# Adafruit_Speaker_Bonnet_rev_D.net
KiCad netlist of a schematic drawn in EAGLE
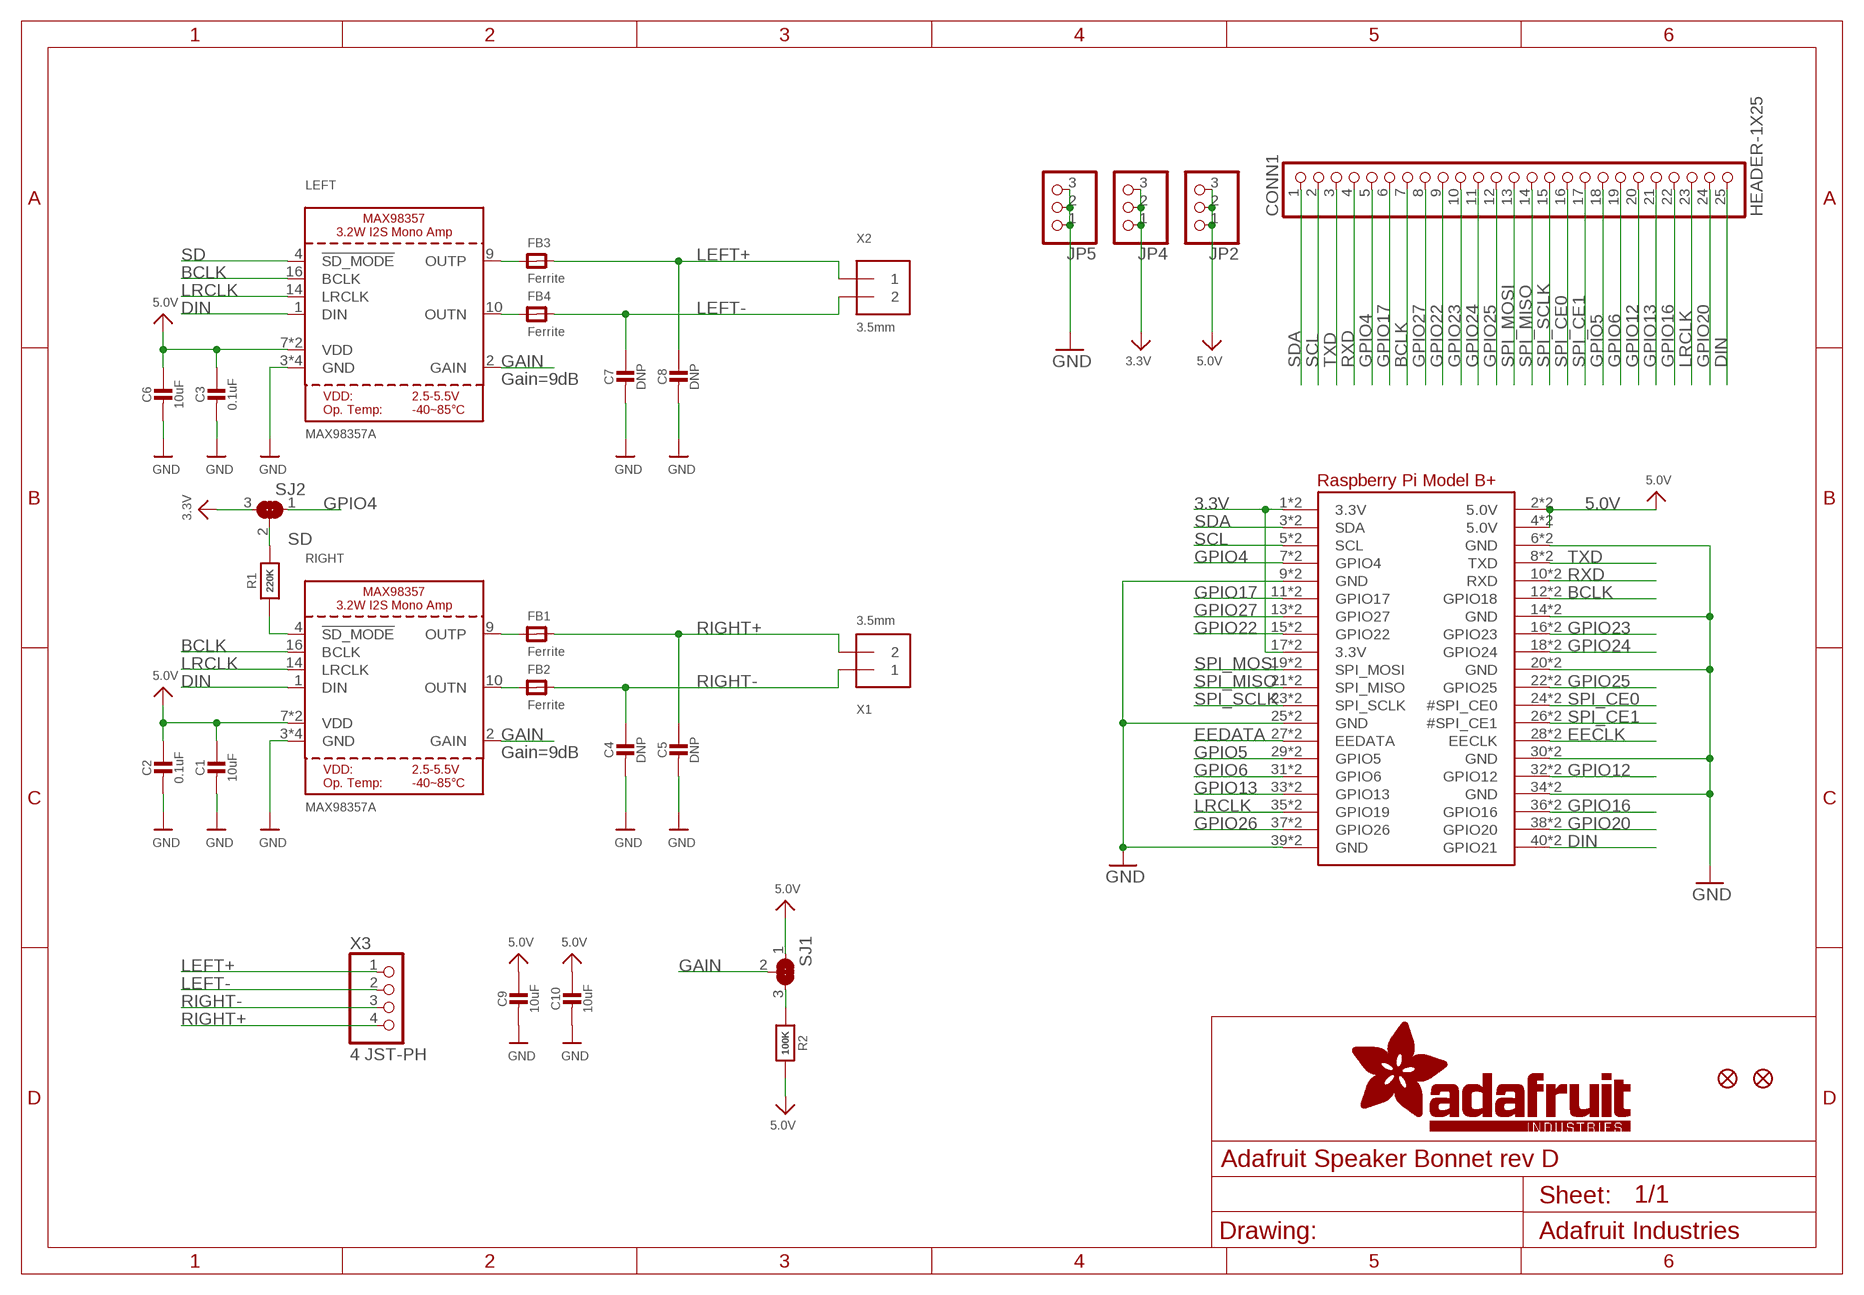
[diagram p0: schematic, sheet 1]

(export (version "E")
  (design (tool "Eeschema 10.0.6"))
  (components
    (comp (ref "C1")
      (value "10uF")
      (footprint "eagle-import:0805-NO")
      (libsource (lib "eagle-import") (part "CAP_CERAMIC0805-NOOUTLINE"))
    )
    (comp (ref "C2")
      (value "0.1uF")
      (footprint "eagle-import:0805-NO")
      (libsource (lib "eagle-import") (part "CAP_CERAMIC0805-NOOUTLINE"))
    )
    (comp (ref "C3")
      (value "0.1uF")
      (footprint "eagle-import:0805-NO")
      (libsource (lib "eagle-import") (part "CAP_CERAMIC0805-NOOUTLINE"))
    )
    (comp (ref "C4")
      (value "DNP")
      (footprint "eagle-import:0805-NO")
      (libsource (lib "eagle-import") (part "CAP_CERAMIC0805-NOOUTLINE"))
    )
    (comp (ref "C5")
      (value "DNP")
      (footprint "eagle-import:0805-NO")
      (libsource (lib "eagle-import") (part "CAP_CERAMIC0805-NOOUTLINE"))
    )
    (comp (ref "C6")
      (value "10uF")
      (footprint "eagle-import:0805-NO")
      (libsource (lib "eagle-import") (part "CAP_CERAMIC0805-NOOUTLINE"))
    )
    (comp (ref "C7")
      (value "DNP")
      (footprint "eagle-import:0805-NO")
      (libsource (lib "eagle-import") (part "CAP_CERAMIC0805-NOOUTLINE"))
    )
    (comp (ref "C8")
      (value "DNP")
      (footprint "eagle-import:0805-NO")
      (libsource (lib "eagle-import") (part "CAP_CERAMIC0805-NOOUTLINE"))
    )
    (comp (ref "C9")
      (value "10uF")
      (footprint "eagle-import:0805-NO")
      (libsource (lib "eagle-import") (part "CAP_CERAMIC0805-NOOUTLINE"))
    )
    (comp (ref "C10")
      (value "10uF")
      (footprint "eagle-import:0805-NO")
      (libsource (lib "eagle-import") (part "CAP_CERAMIC0805-NOOUTLINE"))
    )
    (comp (ref "CONN1")
      (value "HEADER-1X25")
      (footprint "eagle-import:1X25_ROUND_70MIL")
      (libsource (lib "eagle-import") (part "HEADER-1X25"))
    )
    (comp (ref "FB1")
      (value "Ferrite")
      (footprint "eagle-import:0805-NO")
      (libsource (lib "eagle-import") (part "FERRITE-0805NO"))
    )
    (comp (ref "FB2")
      (value "Ferrite")
      (footprint "eagle-import:0805-NO")
      (libsource (lib "eagle-import") (part "FERRITE-0805NO"))
    )
    (comp (ref "FB3")
      (value "Ferrite")
      (footprint "eagle-import:0805-NO")
      (libsource (lib "eagle-import") (part "FERRITE-0805NO"))
    )
    (comp (ref "FB4")
      (value "Ferrite")
      (footprint "eagle-import:0805-NO")
      (libsource (lib "eagle-import") (part "FERRITE-0805NO"))
    )
    (comp (ref "FID1")
      (value "FIDUCIAL_1MM")
      (footprint "eagle-import:FIDUCIAL_1MM")
      (libsource (lib "eagle-import") (part "FIDUCIAL_1MM"))
    )
    (comp (ref "FID2")
      (value "FIDUCIAL_1MM")
      (footprint "eagle-import:FIDUCIAL_1MM")
      (libsource (lib "eagle-import") (part "FIDUCIAL_1MM"))
    )
    (comp (ref "JP2")
      (value "HEADER-1X376MIL")
      (footprint "eagle-import:1X03_ROUND_76")
      (libsource (lib "eagle-import") (part "HEADER-1X376MIL"))
    )
    (comp (ref "JP4")
      (value "HEADER-1X376MIL")
      (footprint "eagle-import:1X03_ROUND_76")
      (libsource (lib "eagle-import") (part "HEADER-1X376MIL"))
    )
    (comp (ref "JP5")
      (value "HEADER-1X376MIL")
      (footprint "eagle-import:1X03_ROUND_76")
      (libsource (lib "eagle-import") (part "HEADER-1X376MIL"))
    )
    (comp (ref "LEFT")
      (value "MAX98357A")
      (footprint "eagle-import:QFN16_3MM")
      (libsource (lib "eagle-import") (part "AUDIOAMP_MAX98357"))
    )
    (comp (ref "R1")
      (value "220K")
      (footprint "eagle-import:0805-NO")
      (libsource (lib "eagle-import") (part "RESISTOR0805_NOOUTLINE"))
    )
    (comp (ref "R2")
      (value "100K")
      (footprint "eagle-import:0805-NO")
      (libsource (lib "eagle-import") (part "RESISTOR0805_NOOUTLINE"))
    )
    (comp (ref "RIGHT")
      (value "MAX98357A")
      (footprint "eagle-import:QFN16_3MM")
      (libsource (lib "eagle-import") (part "AUDIOAMP_MAX98357"))
    )
    (comp (ref "RPI1")
      (value "RASPBERRYPI_BPLUS_BONNET_THMSMT")
      (footprint "eagle-import:PI_BONNET_THMSMT")
      (libsource (lib "eagle-import") (part "RASPBERRYPI_BPLUS_BONNET_THMSMT"))
    )
    (comp (ref "SJ1")
      (value "SOLDERJUMPER_2WAY")
      (footprint "eagle-import:SOLDERJUMPER_2WAY_OPEN_NOPASTE")
      (libsource (lib "eagle-import") (part "SOLDERJUMPER_2WAY"))
    )
    (comp (ref "SJ2")
      (value "SOLDERJUMPER_2WAY")
      (footprint "eagle-import:SOLDERJUMPER_2WAY_OPEN_NOPASTE")
      (libsource (lib "eagle-import") (part "SOLDERJUMPER_2WAY"))
    )
    (comp (ref "X1")
      (value "3.5mm")
      (footprint "eagle-import:TERMBLOCK_1X2-3.5MM")
      (fields (field (name "ROT") "0"))
      (libsource (lib "eagle-import") (part "TERMBLOCK_1X2_3.5MM"))
    )
    (comp (ref "X2")
      (value "3.5mm")
      (footprint "eagle-import:TERMBLOCK_1X2-3.5MM")
      (fields (field (name "ROT") "0"))
      (libsource (lib "eagle-import") (part "TERMBLOCK_1X2_3.5MM"))
    )
    (comp (ref "X3")
      (value "4 JST-PH")
      (footprint "eagle-import:JSTPH4")
      (libsource (lib "eagle-import") (part "CON_JST_PH_4PIN"))
    )
  )
  (nets
    (net (code "1") (name "/BCLK") (class "Default")
      (node (ref "CONN1") (pin "7") (pinfunction "7_7") (pintype "passive"))
      (node (ref "LEFT") (pin "16") (pinfunction "BCLK_16") (pintype "bidirectional"))
      (node (ref "RIGHT") (pin "16") (pinfunction "BCLK_16") (pintype "bidirectional"))
      (node (ref "RPI1") (pin "12") (pinfunction "GPIO18_12") (pintype "bidirectional"))
      (node (ref "RPI1") (pin "S12") (pinfunction "GPIO18_S12") (pintype "bidirectional"))
    )
    (net (code "2") (name "/DIN") (class "Default")
      (node (ref "CONN1") (pin "25") (pinfunction "25_25") (pintype "passive"))
      (node (ref "LEFT") (pin "1") (pinfunction "DIN_1") (pintype "bidirectional"))
      (node (ref "RIGHT") (pin "1") (pinfunction "DIN_1") (pintype "bidirectional"))
      (node (ref "RPI1") (pin "40") (pinfunction "GPIO21_40") (pintype "bidirectional"))
      (node (ref "RPI1") (pin "S40") (pinfunction "GPIO21_S40") (pintype "bidirectional"))
    )
    (net (code "3") (name "/EECLK") (class "Default")
      (node (ref "RPI1") (pin "28") (pinfunction "EECLK_28") (pintype "bidirectional"))
      (node (ref "RPI1") (pin "S28") (pinfunction "EECLK_S28") (pintype "bidirectional"))
    )
    (net (code "4") (name "/EEDATA") (class "Default")
      (node (ref "RPI1") (pin "27") (pinfunction "EEDATA_27") (pintype "bidirectional"))
      (node (ref "RPI1") (pin "S27") (pinfunction "EEDATA_S27") (pintype "bidirectional"))
    )
    (net (code "5") (name "/GAIN") (class "Default")
      (node (ref "LEFT") (pin "2") (pinfunction "GAIN_2") (pintype "bidirectional"))
      (node (ref "RIGHT") (pin "2") (pinfunction "GAIN_2") (pintype "bidirectional"))
      (node (ref "SJ1") (pin "2") (pinfunction "2_2") (pintype "passive"))
    )
    (net (code "6") (name "/GPIO4") (class "Default")
      (node (ref "CONN1") (pin "5") (pinfunction "5_5") (pintype "passive"))
      (node (ref "RPI1") (pin "7") (pinfunction "GPIO4_7") (pintype "bidirectional"))
      (node (ref "RPI1") (pin "S7") (pinfunction "GPIO4_S7") (pintype "bidirectional"))
      (node (ref "SJ2") (pin "1") (pinfunction "1_1") (pintype "passive"))
    )
    (net (code "7") (name "/GPIO5") (class "Default")
      (node (ref "CONN1") (pin "18") (pinfunction "18_18") (pintype "passive"))
      (node (ref "RPI1") (pin "29") (pinfunction "GPIO5_29") (pintype "bidirectional"))
      (node (ref "RPI1") (pin "S29") (pinfunction "GPIO5_S29") (pintype "bidirectional"))
    )
    (net (code "8") (name "/GPIO6") (class "Default")
      (node (ref "CONN1") (pin "19") (pinfunction "19_19") (pintype "passive"))
      (node (ref "RPI1") (pin "31") (pinfunction "GPIO6_31") (pintype "bidirectional"))
      (node (ref "RPI1") (pin "S31") (pinfunction "GPIO6_S31") (pintype "bidirectional"))
    )
    (net (code "9") (name "/GPIO12") (class "Default")
      (node (ref "CONN1") (pin "20") (pinfunction "20_20") (pintype "passive"))
      (node (ref "RPI1") (pin "32") (pinfunction "GPIO12_32") (pintype "bidirectional"))
      (node (ref "RPI1") (pin "S32") (pinfunction "GPIO12_S32") (pintype "bidirectional"))
    )
    (net (code "10") (name "/GPIO13") (class "Default")
      (node (ref "CONN1") (pin "21") (pinfunction "21_21") (pintype "passive"))
      (node (ref "RPI1") (pin "33") (pinfunction "GPIO13_33") (pintype "bidirectional"))
      (node (ref "RPI1") (pin "S33") (pinfunction "GPIO13_S33") (pintype "bidirectional"))
    )
    (net (code "11") (name "/GPIO16") (class "Default")
      (node (ref "CONN1") (pin "22") (pinfunction "22_22") (pintype "passive"))
      (node (ref "RPI1") (pin "36") (pinfunction "GPIO16_36") (pintype "bidirectional"))
      (node (ref "RPI1") (pin "S36") (pinfunction "GPIO16_S36") (pintype "bidirectional"))
    )
    (net (code "12") (name "/GPIO17") (class "Default")
      (node (ref "CONN1") (pin "6") (pinfunction "6_6") (pintype "passive"))
      (node (ref "RPI1") (pin "11") (pinfunction "GPIO17_11") (pintype "bidirectional"))
      (node (ref "RPI1") (pin "S11") (pinfunction "GPIO17_S11") (pintype "bidirectional"))
    )
    (net (code "13") (name "/GPIO20") (class "Default")
      (node (ref "CONN1") (pin "24") (pinfunction "24_24") (pintype "passive"))
      (node (ref "RPI1") (pin "38") (pinfunction "GPIO20_38") (pintype "bidirectional"))
      (node (ref "RPI1") (pin "S38") (pinfunction "GPIO20_S38") (pintype "bidirectional"))
    )
    (net (code "14") (name "/GPIO22") (class "Default")
      (node (ref "CONN1") (pin "9") (pinfunction "9_9") (pintype "passive"))
      (node (ref "RPI1") (pin "15") (pinfunction "GPIO22_15") (pintype "bidirectional"))
      (node (ref "RPI1") (pin "S15") (pinfunction "GPIO22_S15") (pintype "bidirectional"))
    )
    (net (code "15") (name "/GPIO23") (class "Default")
      (node (ref "CONN1") (pin "10") (pinfunction "10_10") (pintype "passive"))
      (node (ref "RPI1") (pin "16") (pinfunction "GPIO23_16") (pintype "bidirectional"))
      (node (ref "RPI1") (pin "S16") (pinfunction "GPIO23_S16") (pintype "bidirectional"))
    )
    (net (code "16") (name "/GPIO24") (class "Default")
      (node (ref "CONN1") (pin "11") (pinfunction "11_11") (pintype "passive"))
      (node (ref "RPI1") (pin "18") (pinfunction "GPIO24_18") (pintype "bidirectional"))
      (node (ref "RPI1") (pin "S18") (pinfunction "GPIO24_S18") (pintype "bidirectional"))
    )
    (net (code "17") (name "/GPIO25") (class "Default")
      (node (ref "CONN1") (pin "12") (pinfunction "12_12") (pintype "passive"))
      (node (ref "RPI1") (pin "22") (pinfunction "GPIO25_22") (pintype "bidirectional"))
      (node (ref "RPI1") (pin "S22") (pinfunction "GPIO25_S22") (pintype "bidirectional"))
    )
    (net (code "18") (name "/GPIO26") (class "Default")
      (node (ref "RPI1") (pin "37") (pinfunction "GPIO26_37") (pintype "bidirectional"))
      (node (ref "RPI1") (pin "S37") (pinfunction "GPIO26_S37") (pintype "bidirectional"))
    )
    (net (code "19") (name "/GPIO27") (class "Default")
      (node (ref "CONN1") (pin "8") (pinfunction "8_8") (pintype "passive"))
      (node (ref "RPI1") (pin "13") (pinfunction "GPIO27_13") (pintype "bidirectional"))
      (node (ref "RPI1") (pin "S13") (pinfunction "GPIO27_S13") (pintype "bidirectional"))
    )
    (net (code "20") (name "/LEFT+") (class "Default")
      (node (ref "C8") (pin "1") (pinfunction "1_1") (pintype "passive"))
      (node (ref "FB3") (pin "2") (pinfunction "P$2_2") (pintype "passive"))
      (node (ref "X2") (pin "1") (pinfunction "1_1") (pintype "passive"))
      (node (ref "X3") (pin "1") (pinfunction "1_1") (pintype "passive"))
    )
    (net (code "21") (name "/LEFT-") (class "Default")
      (node (ref "C7") (pin "1") (pinfunction "1_1") (pintype "passive"))
      (node (ref "FB4") (pin "2") (pinfunction "P$2_2") (pintype "passive"))
      (node (ref "X2") (pin "2") (pinfunction "2_2") (pintype "passive"))
      (node (ref "X3") (pin "2") (pinfunction "2_2") (pintype "passive"))
    )
    (net (code "22") (name "/LRCLK") (class "Default")
      (node (ref "CONN1") (pin "23") (pinfunction "23_23") (pintype "passive"))
      (node (ref "LEFT") (pin "14") (pinfunction "LRCLK_14") (pintype "bidirectional"))
      (node (ref "RIGHT") (pin "14") (pinfunction "LRCLK_14") (pintype "bidirectional"))
      (node (ref "RPI1") (pin "35") (pinfunction "GPIO19_35") (pintype "bidirectional"))
      (node (ref "RPI1") (pin "S35") (pinfunction "GPIO19_S35") (pintype "bidirectional"))
    )
    (net (code "23") (name "/RIGHT+") (class "Default")
      (node (ref "C5") (pin "1") (pinfunction "1_1") (pintype "passive"))
      (node (ref "FB1") (pin "2") (pinfunction "P$2_2") (pintype "passive"))
      (node (ref "X1") (pin "2") (pinfunction "2_2") (pintype "passive"))
      (node (ref "X3") (pin "4") (pinfunction "4_4") (pintype "passive"))
    )
    (net (code "24") (name "/RIGHT-") (class "Default")
      (node (ref "C4") (pin "1") (pinfunction "1_1") (pintype "passive"))
      (node (ref "FB2") (pin "2") (pinfunction "P$2_2") (pintype "passive"))
      (node (ref "X1") (pin "1") (pinfunction "1_1") (pintype "passive"))
      (node (ref "X3") (pin "3") (pinfunction "3_3") (pintype "passive"))
    )
    (net (code "25") (name "/RXD") (class "Default")
      (node (ref "CONN1") (pin "4") (pinfunction "4_4") (pintype "passive"))
      (node (ref "RPI1") (pin "10") (pinfunction "RXD_10") (pintype "bidirectional"))
      (node (ref "RPI1") (pin "S10") (pinfunction "RXD_S10") (pintype "bidirectional"))
    )
    (net (code "26") (name "/SCL") (class "Default")
      (node (ref "CONN1") (pin "2") (pinfunction "2_2") (pintype "passive"))
      (node (ref "RPI1") (pin "5") (pinfunction "SCL_5") (pintype "bidirectional"))
      (node (ref "RPI1") (pin "S5") (pinfunction "SCL_S5") (pintype "bidirectional"))
    )
    (net (code "27") (name "/SD") (class "Default")
      (node (ref "LEFT") (pin "4") (pinfunction "~{SD_MODE}_4") (pintype "bidirectional"))
      (node (ref "R1") (pin "2") (pinfunction "2_2") (pintype "passive"))
      (node (ref "SJ2") (pin "2") (pinfunction "2_2") (pintype "passive"))
    )
    (net (code "28") (name "/SDA") (class "Default")
      (node (ref "CONN1") (pin "1") (pinfunction "1_1") (pintype "passive"))
      (node (ref "RPI1") (pin "3") (pinfunction "SDA_3") (pintype "bidirectional"))
      (node (ref "RPI1") (pin "S3") (pinfunction "SDA_S3") (pintype "bidirectional"))
    )
    (net (code "29") (name "/SPI_CE0") (class "Default")
      (node (ref "CONN1") (pin "16") (pinfunction "16_16") (pintype "passive"))
      (node (ref "RPI1") (pin "24") (pinfunction "#SPI_CE0_24") (pintype "bidirectional"))
      (node (ref "RPI1") (pin "S24") (pinfunction "#SPI_CE0_S24") (pintype "bidirectional"))
    )
    (net (code "30") (name "/SPI_CE1") (class "Default")
      (node (ref "CONN1") (pin "17") (pinfunction "17_17") (pintype "passive"))
      (node (ref "RPI1") (pin "26") (pinfunction "#SPI_CE1_26") (pintype "bidirectional"))
      (node (ref "RPI1") (pin "S26") (pinfunction "#SPI_CE1_S26") (pintype "bidirectional"))
    )
    (net (code "31") (name "/SPI_MISO") (class "Default")
      (node (ref "CONN1") (pin "14") (pinfunction "14_14") (pintype "passive"))
      (node (ref "RPI1") (pin "21") (pinfunction "SPI_MISO_21") (pintype "bidirectional"))
      (node (ref "RPI1") (pin "S21") (pinfunction "SPI_MISO_S21") (pintype "bidirectional"))
    )
    (net (code "32") (name "/SPI_MOSI") (class "Default")
      (node (ref "CONN1") (pin "13") (pinfunction "13_13") (pintype "passive"))
      (node (ref "RPI1") (pin "19") (pinfunction "SPI_MOSI_19") (pintype "bidirectional"))
      (node (ref "RPI1") (pin "S19") (pinfunction "SPI_MOSI_S19") (pintype "bidirectional"))
    )
    (net (code "33") (name "/SPI_SCLK") (class "Default")
      (node (ref "CONN1") (pin "15") (pinfunction "15_15") (pintype "passive"))
      (node (ref "RPI1") (pin "23") (pinfunction "SPI_SCLK_23") (pintype "bidirectional"))
      (node (ref "RPI1") (pin "S23") (pinfunction "SPI_SCLK_S23") (pintype "bidirectional"))
    )
    (net (code "34") (name "/TXD") (class "Default")
      (node (ref "CONN1") (pin "3") (pinfunction "3_3") (pintype "passive"))
      (node (ref "RPI1") (pin "8") (pinfunction "TXD_8") (pintype "bidirectional"))
      (node (ref "RPI1") (pin "S8") (pinfunction "TXD_S8") (pintype "bidirectional"))
    )
    (net (code "35") (name "3.3V") (class "Default")
      (node (ref "JP4") (pin "1") (pinfunction "1_1") (pintype "passive"))
      (node (ref "JP4") (pin "2") (pinfunction "2_2") (pintype "passive"))
      (node (ref "JP4") (pin "3") (pinfunction "3_3") (pintype "passive"))
      (node (ref "RPI1") (pin "1") (pinfunction "3.3V_1") (pintype "power_in"))
      (node (ref "RPI1") (pin "17") (pinfunction "3.3V_17") (pintype "power_in"))
      (node (ref "RPI1") (pin "S1") (pinfunction "3.3V_S1") (pintype "power_in"))
      (node (ref "RPI1") (pin "S17") (pinfunction "3.3V_S17") (pintype "power_in"))
      (node (ref "SJ2") (pin "3") (pinfunction "3_3") (pintype "passive"))
    )
    (net (code "36") (name "5.0V") (class "Default")
      (node (ref "C1") (pin "1") (pinfunction "1_1") (pintype "passive"))
      (node (ref "C10") (pin "1") (pinfunction "1_1") (pintype "passive"))
      (node (ref "C2") (pin "1") (pinfunction "1_1") (pintype "passive"))
      (node (ref "C3") (pin "1") (pinfunction "1_1") (pintype "passive"))
      (node (ref "C6") (pin "1") (pinfunction "1_1") (pintype "passive"))
      (node (ref "C9") (pin "1") (pinfunction "1_1") (pintype "passive"))
      (node (ref "JP2") (pin "1") (pinfunction "1_1") (pintype "passive"))
      (node (ref "JP2") (pin "2") (pinfunction "2_2") (pintype "passive"))
      (node (ref "JP2") (pin "3") (pinfunction "3_3") (pintype "passive"))
      (node (ref "LEFT") (pin "7") (pinfunction "VDD_7") (pintype "power_in"))
      (node (ref "LEFT") (pin "8") (pinfunction "VDD_8") (pintype "power_in"))
      (node (ref "R2") (pin "2") (pinfunction "2_2") (pintype "passive"))
      (node (ref "RIGHT") (pin "7") (pinfunction "VDD_7") (pintype "power_in"))
      (node (ref "RIGHT") (pin "8") (pinfunction "VDD_8") (pintype "power_in"))
      (node (ref "RPI1") (pin "2") (pinfunction "5.0V_2") (pintype "power_in"))
      (node (ref "RPI1") (pin "4") (pinfunction "5.0V_4") (pintype "power_in"))
      (node (ref "RPI1") (pin "S2") (pinfunction "5.0V_S2") (pintype "power_in"))
      (node (ref "RPI1") (pin "S4") (pinfunction "5.0V_S4") (pintype "power_in"))
      (node (ref "SJ1") (pin "1") (pinfunction "1_1") (pintype "passive"))
    )
    (net (code "37") (name "GND") (class "Default")
      (node (ref "C1") (pin "2") (pinfunction "2_2") (pintype "passive"))
      (node (ref "C10") (pin "2") (pinfunction "2_2") (pintype "passive"))
      (node (ref "C2") (pin "2") (pinfunction "2_2") (pintype "passive"))
      (node (ref "C3") (pin "2") (pinfunction "2_2") (pintype "passive"))
      (node (ref "C4") (pin "2") (pinfunction "2_2") (pintype "passive"))
      (node (ref "C5") (pin "2") (pinfunction "2_2") (pintype "passive"))
      (node (ref "C6") (pin "2") (pinfunction "2_2") (pintype "passive"))
      (node (ref "C7") (pin "2") (pinfunction "2_2") (pintype "passive"))
      (node (ref "C8") (pin "2") (pinfunction "2_2") (pintype "passive"))
      (node (ref "C9") (pin "2") (pinfunction "2_2") (pintype "passive"))
      (node (ref "JP5") (pin "1") (pinfunction "1_1") (pintype "passive"))
      (node (ref "JP5") (pin "2") (pinfunction "2_2") (pintype "passive"))
      (node (ref "JP5") (pin "3") (pinfunction "3_3") (pintype "passive"))
      (node (ref "LEFT") (pin "11") (pinfunction "GND_11") (pintype "power_in"))
      (node (ref "LEFT") (pin "15") (pinfunction "GND_15") (pintype "power_in"))
      (node (ref "LEFT") (pin "3") (pinfunction "GND_3") (pintype "power_in"))
      (node (ref "LEFT") (pin "THERMAL") (pinfunction "GND_THERMAL") (pintype "power_in"))
      (node (ref "RIGHT") (pin "11") (pinfunction "GND_11") (pintype "power_in"))
      (node (ref "RIGHT") (pin "15") (pinfunction "GND_15") (pintype "power_in"))
      (node (ref "RIGHT") (pin "3") (pinfunction "GND_3") (pintype "power_in"))
      (node (ref "RIGHT") (pin "THERMAL") (pinfunction "GND_THERMAL") (pintype "power_in"))
      (node (ref "RPI1") (pin "14") (pinfunction "GND_14") (pintype "power_in"))
      (node (ref "RPI1") (pin "20") (pinfunction "GND_20") (pintype "power_in"))
      (node (ref "RPI1") (pin "25") (pinfunction "GND_25") (pintype "power_in"))
      (node (ref "RPI1") (pin "30") (pinfunction "GND_30") (pintype "power_in"))
      (node (ref "RPI1") (pin "34") (pinfunction "GND_34") (pintype "power_in"))
      (node (ref "RPI1") (pin "39") (pinfunction "GND_39") (pintype "power_in"))
      (node (ref "RPI1") (pin "6") (pinfunction "GND_6") (pintype "power_in"))
      (node (ref "RPI1") (pin "9") (pinfunction "GND_9") (pintype "power_in"))
      (node (ref "RPI1") (pin "S14") (pinfunction "GND_S14") (pintype "power_in"))
      (node (ref "RPI1") (pin "S20") (pinfunction "GND_S20") (pintype "power_in"))
      (node (ref "RPI1") (pin "S25") (pinfunction "GND_S25") (pintype "power_in"))
      (node (ref "RPI1") (pin "S30") (pinfunction "GND_S30") (pintype "power_in"))
      (node (ref "RPI1") (pin "S34") (pinfunction "GND_S34") (pintype "power_in"))
      (node (ref "RPI1") (pin "S39") (pinfunction "GND_S39") (pintype "power_in"))
      (node (ref "RPI1") (pin "S6") (pinfunction "GND_S6") (pintype "power_in"))
      (node (ref "RPI1") (pin "S9") (pinfunction "GND_S9") (pintype "power_in"))
    )
    (net (code "38") (name "Net-(FB1-P$1)") (class "Default")
      (node (ref "FB1") (pin "1") (pinfunction "P$1_1") (pintype "passive"))
      (node (ref "RIGHT") (pin "9") (pinfunction "OUTP_9") (pintype "output"))
    )
    (net (code "39") (name "Net-(FB2-P$1)") (class "Default")
      (node (ref "FB2") (pin "1") (pinfunction "P$1_1") (pintype "passive"))
      (node (ref "RIGHT") (pin "10") (pinfunction "OUTN_10") (pintype "output"))
    )
    (net (code "40") (name "Net-(FB3-P$1)") (class "Default")
      (node (ref "FB3") (pin "1") (pinfunction "P$1_1") (pintype "passive"))
      (node (ref "LEFT") (pin "9") (pinfunction "OUTP_9") (pintype "output"))
    )
    (net (code "41") (name "Net-(FB4-P$1)") (class "Default")
      (node (ref "FB4") (pin "1") (pinfunction "P$1_1") (pintype "passive"))
      (node (ref "LEFT") (pin "10") (pinfunction "OUTN_10") (pintype "output"))
    )
    (net (code "42") (name "Net-(R2-Pad1)") (class "Default")
      (node (ref "R2") (pin "1") (pinfunction "1_1") (pintype "passive"))
      (node (ref "SJ1") (pin "3") (pinfunction "3_3") (pintype "passive"))
    )
    (net (code "43") (name "Net-(RIGHT-~{SD_MODE})") (class "Default")
      (node (ref "R1") (pin "1") (pinfunction "1_1") (pintype "passive"))
      (node (ref "RIGHT") (pin "4") (pinfunction "~{SD_MODE}_4") (pintype "bidirectional"))
    )
  )
)
